# BottomSide.net
KiCad netlist of a schematic drawn in Altium Designer
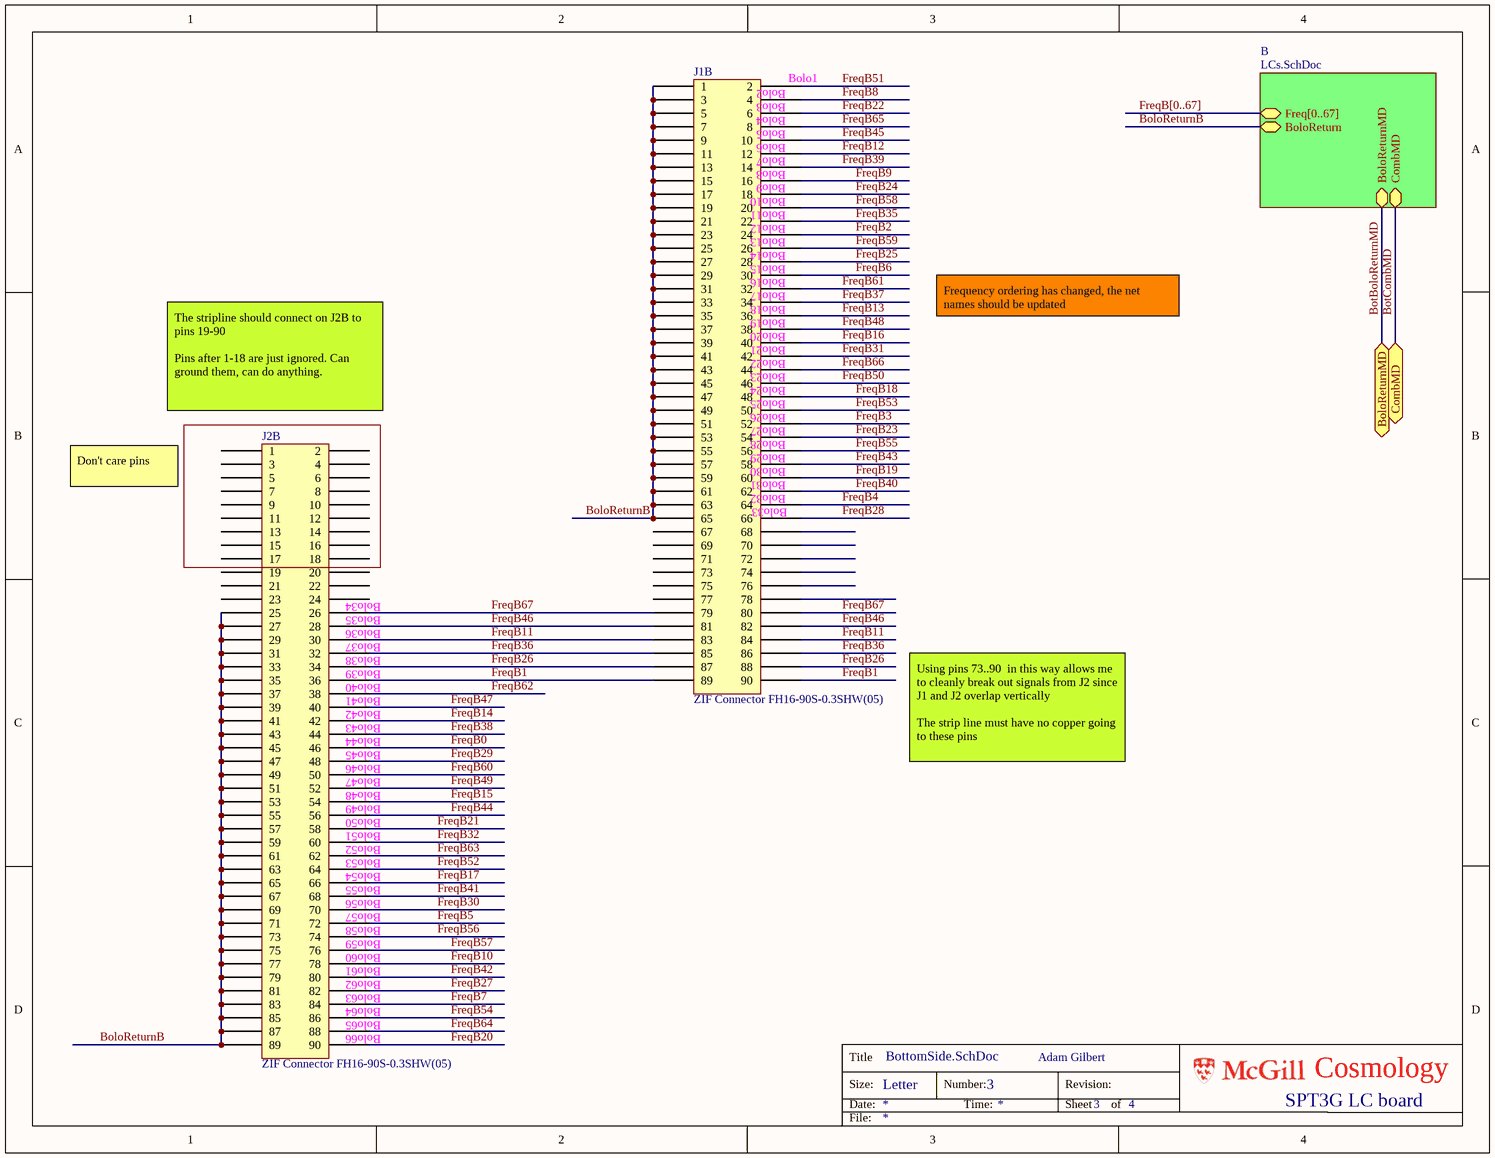
[diagram p0: BottomSide.SchDoc]

(export (version "E")
  (design (tool "Eeschema 10.0.6"))
  (components
    (comp (ref "J1B")
      (value "ZIF Connector FH16-90S-0.3SHW(05)")
      (footprint "LCBoard_ZIFCon")
      (libsource (lib "SPT3G_LCBoard") (part "LCboard_FH16-90S-0.3SHW(05)"))
    )
    (comp (ref "J2B")
      (value "ZIF Connector FH16-90S-0.3SHW(05)")
      (footprint "LCBoard_ZIFCon")
      (libsource (lib "SPT3G_LCBoard") (part "LCboard_FH16-90S-0.3SHW(05)"))
    )
  )
  (nets
    (net (code "3") (name "/BoloReturnB") (class "Default")
      (node (ref "J1B") (pin "1") (pinfunction "1_1") (pintype "passive"))
      (node (ref "J1B") (pin "11") (pinfunction "11_11") (pintype "passive"))
      (node (ref "J1B") (pin "13") (pinfunction "13_13") (pintype "passive"))
      (node (ref "J1B") (pin "15") (pinfunction "15_15") (pintype "passive"))
      (node (ref "J1B") (pin "17") (pinfunction "17_17") (pintype "passive"))
      (node (ref "J1B") (pin "19") (pinfunction "19_19") (pintype "passive"))
      (node (ref "J1B") (pin "21") (pinfunction "21_21") (pintype "passive"))
      (node (ref "J1B") (pin "23") (pinfunction "23_23") (pintype "passive"))
      (node (ref "J1B") (pin "25") (pinfunction "25_25") (pintype "passive"))
      (node (ref "J1B") (pin "27") (pinfunction "27_27") (pintype "passive"))
      (node (ref "J1B") (pin "29") (pinfunction "29_29") (pintype "passive"))
      (node (ref "J1B") (pin "3") (pinfunction "3_3") (pintype "passive"))
      (node (ref "J1B") (pin "31") (pinfunction "31_31") (pintype "passive"))
      (node (ref "J1B") (pin "33") (pinfunction "33_33") (pintype "passive"))
      (node (ref "J1B") (pin "35") (pinfunction "35_35") (pintype "passive"))
      (node (ref "J1B") (pin "37") (pinfunction "37_37") (pintype "passive"))
      (node (ref "J1B") (pin "39") (pinfunction "39_39") (pintype "passive"))
      (node (ref "J1B") (pin "41") (pinfunction "41_41") (pintype "passive"))
      (node (ref "J1B") (pin "43") (pinfunction "43_43") (pintype "passive"))
      (node (ref "J1B") (pin "45") (pinfunction "45_45") (pintype "passive"))
      (node (ref "J1B") (pin "47") (pinfunction "47_47") (pintype "passive"))
      (node (ref "J1B") (pin "49") (pinfunction "49_49") (pintype "passive"))
      (node (ref "J1B") (pin "5") (pinfunction "5_5") (pintype "passive"))
      (node (ref "J1B") (pin "51") (pinfunction "51_51") (pintype "passive"))
      (node (ref "J1B") (pin "53") (pinfunction "53_53") (pintype "passive"))
      (node (ref "J1B") (pin "55") (pinfunction "55_55") (pintype "passive"))
      (node (ref "J1B") (pin "57") (pinfunction "57_57") (pintype "passive"))
      (node (ref "J1B") (pin "59") (pinfunction "59_59") (pintype "passive"))
      (node (ref "J1B") (pin "61") (pinfunction "61_61") (pintype "passive"))
      (node (ref "J1B") (pin "63") (pinfunction "63_63") (pintype "passive"))
      (node (ref "J1B") (pin "65") (pinfunction "65_65") (pintype "passive"))
      (node (ref "J1B") (pin "7") (pinfunction "7_7") (pintype "passive"))
      (node (ref "J1B") (pin "9") (pinfunction "9_9") (pintype "passive"))
      (node (ref "J2B") (pin "25") (pinfunction "25_25") (pintype "passive"))
      (node (ref "J2B") (pin "27") (pinfunction "27_27") (pintype "passive"))
      (node (ref "J2B") (pin "29") (pinfunction "29_29") (pintype "passive"))
      (node (ref "J2B") (pin "31") (pinfunction "31_31") (pintype "passive"))
      (node (ref "J2B") (pin "33") (pinfunction "33_33") (pintype "passive"))
      (node (ref "J2B") (pin "35") (pinfunction "35_35") (pintype "passive"))
      (node (ref "J2B") (pin "37") (pinfunction "37_37") (pintype "passive"))
      (node (ref "J2B") (pin "39") (pinfunction "39_39") (pintype "passive"))
      (node (ref "J2B") (pin "41") (pinfunction "41_41") (pintype "passive"))
      (node (ref "J2B") (pin "43") (pinfunction "43_43") (pintype "passive"))
      (node (ref "J2B") (pin "45") (pinfunction "45_45") (pintype "passive"))
      (node (ref "J2B") (pin "47") (pinfunction "47_47") (pintype "passive"))
      (node (ref "J2B") (pin "49") (pinfunction "49_49") (pintype "passive"))
      (node (ref "J2B") (pin "51") (pinfunction "51_51") (pintype "passive"))
      (node (ref "J2B") (pin "53") (pinfunction "53_53") (pintype "passive"))
      (node (ref "J2B") (pin "55") (pinfunction "55_55") (pintype "passive"))
      (node (ref "J2B") (pin "57") (pinfunction "57_57") (pintype "passive"))
      (node (ref "J2B") (pin "59") (pinfunction "59_59") (pintype "passive"))
      (node (ref "J2B") (pin "61") (pinfunction "61_61") (pintype "passive"))
      (node (ref "J2B") (pin "63") (pinfunction "63_63") (pintype "passive"))
      (node (ref "J2B") (pin "65") (pinfunction "65_65") (pintype "passive"))
      (node (ref "J2B") (pin "67") (pinfunction "67_67") (pintype "passive"))
      (node (ref "J2B") (pin "69") (pinfunction "69_69") (pintype "passive"))
      (node (ref "J2B") (pin "71") (pinfunction "71_71") (pintype "passive"))
      (node (ref "J2B") (pin "73") (pinfunction "73_73") (pintype "passive"))
      (node (ref "J2B") (pin "75") (pinfunction "75_75") (pintype "passive"))
      (node (ref "J2B") (pin "77") (pinfunction "77_77") (pintype "passive"))
      (node (ref "J2B") (pin "79") (pinfunction "79_79") (pintype "passive"))
      (node (ref "J2B") (pin "81") (pinfunction "81_81") (pintype "passive"))
      (node (ref "J2B") (pin "83") (pinfunction "83_83") (pintype "passive"))
      (node (ref "J2B") (pin "85") (pinfunction "85_85") (pintype "passive"))
      (node (ref "J2B") (pin "87") (pinfunction "87_87") (pintype "passive"))
      (node (ref "J2B") (pin "89") (pinfunction "89_89") (pintype "passive"))
    )
    (net (code "6") (name "/FreqB0") (class "Default")
      (node (ref "J2B") (pin "46") (pinfunction "46_46") (pintype "passive"))
    )
    (net (code "7") (name "/FreqB1") (class "Default")
      (node (ref "J1B") (pin "89") (pinfunction "89_89") (pintype "passive"))
      (node (ref "J1B") (pin "90") (pinfunction "90_90") (pintype "passive"))
      (node (ref "J2B") (pin "36") (pinfunction "36_36") (pintype "passive"))
    )
    (net (code "8") (name "/FreqB2") (class "Default")
      (node (ref "J1B") (pin "24") (pinfunction "24_24") (pintype "passive"))
    )
    (net (code "9") (name "/FreqB3") (class "Default")
      (node (ref "J1B") (pin "52") (pinfunction "52_52") (pintype "passive"))
    )
    (net (code "10") (name "/FreqB4") (class "Default")
      (node (ref "J1B") (pin "64") (pinfunction "64_64") (pintype "passive"))
    )
    (net (code "11") (name "/FreqB5") (class "Default")
      (node (ref "J2B") (pin "72") (pinfunction "72_72") (pintype "passive"))
    )
    (net (code "12") (name "/FreqB6") (class "Default")
      (node (ref "J1B") (pin "30") (pinfunction "30_30") (pintype "passive"))
    )
    (net (code "13") (name "/FreqB7") (class "Default")
      (node (ref "J2B") (pin "84") (pinfunction "84_84") (pintype "passive"))
    )
    (net (code "14") (name "/FreqB8") (class "Default")
      (node (ref "J1B") (pin "4") (pinfunction "4_4") (pintype "passive"))
    )
    (net (code "15") (name "/FreqB9") (class "Default")
      (node (ref "J1B") (pin "16") (pinfunction "16_16") (pintype "passive"))
    )
    (net (code "16") (name "/FreqB10") (class "Default")
      (node (ref "J2B") (pin "78") (pinfunction "78_78") (pintype "passive"))
    )
    (net (code "17") (name "/FreqB11") (class "Default")
      (node (ref "J1B") (pin "83") (pinfunction "83_83") (pintype "passive"))
      (node (ref "J1B") (pin "84") (pinfunction "84_84") (pintype "passive"))
      (node (ref "J2B") (pin "30") (pinfunction "30_30") (pintype "passive"))
    )
    (net (code "18") (name "/FreqB12") (class "Default")
      (node (ref "J1B") (pin "12") (pinfunction "12_12") (pintype "passive"))
    )
    (net (code "19") (name "/FreqB13") (class "Default")
      (node (ref "J1B") (pin "36") (pinfunction "36_36") (pintype "passive"))
    )
    (net (code "20") (name "/FreqB14") (class "Default")
      (node (ref "J2B") (pin "42") (pinfunction "42_42") (pintype "passive"))
    )
    (net (code "21") (name "/FreqB15") (class "Default")
      (node (ref "J2B") (pin "54") (pinfunction "54_54") (pintype "passive"))
    )
    (net (code "22") (name "/FreqB16") (class "Default")
      (node (ref "J1B") (pin "40") (pinfunction "40_40") (pintype "passive"))
    )
    (net (code "23") (name "/FreqB17") (class "Default")
      (node (ref "J2B") (pin "66") (pinfunction "66_66") (pintype "passive"))
    )
    (net (code "24") (name "/FreqB18") (class "Default")
      (node (ref "J1B") (pin "48") (pinfunction "48_48") (pintype "passive"))
    )
    (net (code "25") (name "/FreqB19") (class "Default")
      (node (ref "J1B") (pin "60") (pinfunction "60_60") (pintype "passive"))
    )
    (net (code "26") (name "/FreqB20") (class "Default")
      (node (ref "J2B") (pin "90") (pinfunction "90_90") (pintype "passive"))
    )
    (net (code "27") (name "/FreqB21") (class "Default")
      (node (ref "J2B") (pin "58") (pinfunction "58_58") (pintype "passive"))
    )
    (net (code "28") (name "/FreqB22") (class "Default")
      (node (ref "J1B") (pin "6") (pinfunction "6_6") (pintype "passive"))
    )
    (net (code "29") (name "/FreqB23") (class "Default")
      (node (ref "J1B") (pin "54") (pinfunction "54_54") (pintype "passive"))
    )
    (net (code "30") (name "/FreqB24") (class "Default")
      (node (ref "J1B") (pin "18") (pinfunction "18_18") (pintype "passive"))
    )
    (net (code "31") (name "/FreqB25") (class "Default")
      (node (ref "J1B") (pin "28") (pinfunction "28_28") (pintype "passive"))
    )
    (net (code "32") (name "/FreqB26") (class "Default")
      (node (ref "J1B") (pin "87") (pinfunction "87_87") (pintype "passive"))
      (node (ref "J1B") (pin "88") (pinfunction "88_88") (pintype "passive"))
      (node (ref "J2B") (pin "34") (pinfunction "34_34") (pintype "passive"))
    )
    (net (code "33") (name "/FreqB27") (class "Default")
      (node (ref "J2B") (pin "82") (pinfunction "82_82") (pintype "passive"))
    )
    (net (code "34") (name "/FreqB28") (class "Default")
      (node (ref "J1B") (pin "66") (pinfunction "66_66") (pintype "passive"))
    )
    (net (code "35") (name "/FreqB29") (class "Default")
      (node (ref "J2B") (pin "48") (pinfunction "48_48") (pintype "passive"))
    )
    (net (code "36") (name "/FreqB30") (class "Default")
      (node (ref "J2B") (pin "70") (pinfunction "70_70") (pintype "passive"))
    )
    (net (code "37") (name "/FreqB31") (class "Default")
      (node (ref "J1B") (pin "42") (pinfunction "42_42") (pintype "passive"))
    )
    (net (code "38") (name "/FreqB32") (class "Default")
      (node (ref "J2B") (pin "60") (pinfunction "60_60") (pintype "passive"))
    )
    (net (code "39") (name "/FreqB35") (class "Default")
      (node (ref "J1B") (pin "22") (pinfunction "22_22") (pintype "passive"))
    )
    (net (code "40") (name "/FreqB36") (class "Default")
      (node (ref "J1B") (pin "85") (pinfunction "85_85") (pintype "passive"))
      (node (ref "J1B") (pin "86") (pinfunction "86_86") (pintype "passive"))
      (node (ref "J2B") (pin "32") (pinfunction "32_32") (pintype "passive"))
    )
    (net (code "41") (name "/FreqB37") (class "Default")
      (node (ref "J1B") (pin "34") (pinfunction "34_34") (pintype "passive"))
    )
    (net (code "42") (name "/FreqB38") (class "Default")
      (node (ref "J2B") (pin "44") (pinfunction "44_44") (pintype "passive"))
    )
    (net (code "43") (name "/FreqB39") (class "Default")
      (node (ref "J1B") (pin "14") (pinfunction "14_14") (pintype "passive"))
    )
    (net (code "44") (name "/FreqB40") (class "Default")
      (node (ref "J1B") (pin "62") (pinfunction "62_62") (pintype "passive"))
    )
    (net (code "45") (name "/FreqB41") (class "Default")
      (node (ref "J2B") (pin "68") (pinfunction "68_68") (pintype "passive"))
    )
    (net (code "46") (name "/FreqB42") (class "Default")
      (node (ref "J2B") (pin "80") (pinfunction "80_80") (pintype "passive"))
    )
    (net (code "47") (name "/FreqB43") (class "Default")
      (node (ref "J1B") (pin "58") (pinfunction "58_58") (pintype "passive"))
    )
    (net (code "48") (name "/FreqB44") (class "Default")
      (node (ref "J2B") (pin "56") (pinfunction "56_56") (pintype "passive"))
    )
    (net (code "49") (name "/FreqB45") (class "Default")
      (node (ref "J1B") (pin "10") (pinfunction "10_10") (pintype "passive"))
    )
    (net (code "50") (name "/FreqB46") (class "Default")
      (node (ref "J1B") (pin "81") (pinfunction "81_81") (pintype "passive"))
      (node (ref "J1B") (pin "82") (pinfunction "82_82") (pintype "passive"))
      (node (ref "J2B") (pin "28") (pinfunction "28_28") (pintype "passive"))
    )
    (net (code "51") (name "/FreqB47") (class "Default")
      (node (ref "J2B") (pin "40") (pinfunction "40_40") (pintype "passive"))
    )
    (net (code "52") (name "/FreqB48") (class "Default")
      (node (ref "J1B") (pin "38") (pinfunction "38_38") (pintype "passive"))
    )
    (net (code "53") (name "/FreqB49") (class "Default")
      (node (ref "J2B") (pin "52") (pinfunction "52_52") (pintype "passive"))
    )
    (net (code "54") (name "/FreqB50") (class "Default")
      (node (ref "J1B") (pin "46") (pinfunction "46_46") (pintype "passive"))
    )
    (net (code "55") (name "/FreqB51") (class "Default")
      (node (ref "J1B") (pin "2") (pinfunction "2_2") (pintype "passive"))
    )
    (net (code "56") (name "/FreqB52") (class "Default")
      (node (ref "J2B") (pin "64") (pinfunction "64_64") (pintype "passive"))
    )
    (net (code "57") (name "/FreqB53") (class "Default")
      (node (ref "J1B") (pin "50") (pinfunction "50_50") (pintype "passive"))
    )
    (net (code "58") (name "/FreqB54") (class "Default")
      (node (ref "J2B") (pin "86") (pinfunction "86_86") (pintype "passive"))
    )
    (net (code "59") (name "/FreqB55") (class "Default")
      (node (ref "J1B") (pin "56") (pinfunction "56_56") (pintype "passive"))
    )
    (net (code "60") (name "/FreqB56") (class "Default")
      (node (ref "J2B") (pin "74") (pinfunction "74_74") (pintype "passive"))
    )
    (net (code "61") (name "/FreqB57") (class "Default")
      (node (ref "J2B") (pin "76") (pinfunction "76_76") (pintype "passive"))
    )
    (net (code "62") (name "/FreqB58") (class "Default")
      (node (ref "J1B") (pin "20") (pinfunction "20_20") (pintype "passive"))
    )
    (net (code "63") (name "/FreqB59") (class "Default")
      (node (ref "J1B") (pin "26") (pinfunction "26_26") (pintype "passive"))
    )
    (net (code "64") (name "/FreqB60") (class "Default")
      (node (ref "J2B") (pin "50") (pinfunction "50_50") (pintype "passive"))
    )
    (net (code "65") (name "/FreqB61") (class "Default")
      (node (ref "J1B") (pin "32") (pinfunction "32_32") (pintype "passive"))
    )
    (net (code "66") (name "/FreqB62") (class "Default")
      (node (ref "J2B") (pin "38") (pinfunction "38_38") (pintype "passive"))
    )
    (net (code "67") (name "/FreqB63") (class "Default")
      (node (ref "J2B") (pin "62") (pinfunction "62_62") (pintype "passive"))
    )
    (net (code "68") (name "/FreqB64") (class "Default")
      (node (ref "J2B") (pin "88") (pinfunction "88_88") (pintype "passive"))
    )
    (net (code "69") (name "/FreqB65") (class "Default")
      (node (ref "J1B") (pin "8") (pinfunction "8_8") (pintype "passive"))
    )
    (net (code "70") (name "/FreqB66") (class "Default")
      (node (ref "J1B") (pin "44") (pinfunction "44_44") (pintype "passive"))
    )
    (net (code "71") (name "/FreqB67") (class "Default")
      (node (ref "J1B") (pin "79") (pinfunction "79_79") (pintype "passive"))
      (node (ref "J1B") (pin "80") (pinfunction "80_80") (pintype "passive"))
      (node (ref "J2B") (pin "26") (pinfunction "26_26") (pintype "passive"))
    )
    (net (code "73") (name "unconnected-(J1B-Pad67)") (class "Default")
      (node (ref "J1B") (pin "67") (pinfunction "67_67") (pintype "passive"))
    )
    (net (code "74") (name "unconnected-(J1B-Pad68)") (class "Default")
      (node (ref "J1B") (pin "68") (pinfunction "68_68") (pintype "passive"))
    )
    (net (code "75") (name "unconnected-(J1B-Pad69)") (class "Default")
      (node (ref "J1B") (pin "69") (pinfunction "69_69") (pintype "passive"))
    )
    (net (code "76") (name "unconnected-(J1B-Pad70)") (class "Default")
      (node (ref "J1B") (pin "70") (pinfunction "70_70") (pintype "passive"))
    )
    (net (code "77") (name "unconnected-(J1B-Pad71)") (class "Default")
      (node (ref "J1B") (pin "71") (pinfunction "71_71") (pintype "passive"))
    )
    (net (code "78") (name "unconnected-(J1B-Pad72)") (class "Default")
      (node (ref "J1B") (pin "72") (pinfunction "72_72") (pintype "passive"))
    )
    (net (code "79") (name "unconnected-(J1B-Pad73)") (class "Default")
      (node (ref "J1B") (pin "73") (pinfunction "73_73") (pintype "passive"))
    )
    (net (code "80") (name "unconnected-(J1B-Pad74)") (class "Default")
      (node (ref "J1B") (pin "74") (pinfunction "74_74") (pintype "passive"))
    )
    (net (code "81") (name "unconnected-(J1B-Pad75)") (class "Default")
      (node (ref "J1B") (pin "75") (pinfunction "75_75") (pintype "passive"))
    )
    (net (code "82") (name "unconnected-(J1B-Pad76)") (class "Default")
      (node (ref "J1B") (pin "76") (pinfunction "76_76") (pintype "passive"))
    )
    (net (code "83") (name "unconnected-(J1B-Pad77)") (class "Default")
      (node (ref "J1B") (pin "77") (pinfunction "77_77") (pintype "passive"))
    )
    (net (code "84") (name "unconnected-(J1B-Pad78)") (class "Default")
      (node (ref "J1B") (pin "78") (pinfunction "78_78") (pintype "passive"))
    )
    (net (code "85") (name "unconnected-(J2B-Pad1)") (class "Default")
      (node (ref "J2B") (pin "1") (pinfunction "1_1") (pintype "passive"))
    )
    (net (code "86") (name "unconnected-(J2B-Pad2)") (class "Default")
      (node (ref "J2B") (pin "2") (pinfunction "2_2") (pintype "passive"))
    )
    (net (code "87") (name "unconnected-(J2B-Pad3)") (class "Default")
      (node (ref "J2B") (pin "3") (pinfunction "3_3") (pintype "passive"))
    )
    (net (code "88") (name "unconnected-(J2B-Pad4)") (class "Default")
      (node (ref "J2B") (pin "4") (pinfunction "4_4") (pintype "passive"))
    )
    (net (code "89") (name "unconnected-(J2B-Pad5)") (class "Default")
      (node (ref "J2B") (pin "5") (pinfunction "5_5") (pintype "passive"))
    )
    (net (code "90") (name "unconnected-(J2B-Pad6)") (class "Default")
      (node (ref "J2B") (pin "6") (pinfunction "6_6") (pintype "passive"))
    )
    (net (code "91") (name "unconnected-(J2B-Pad7)") (class "Default")
      (node (ref "J2B") (pin "7") (pinfunction "7_7") (pintype "passive"))
    )
    (net (code "92") (name "unconnected-(J2B-Pad8)") (class "Default")
      (node (ref "J2B") (pin "8") (pinfunction "8_8") (pintype "passive"))
    )
    (net (code "93") (name "unconnected-(J2B-Pad9)") (class "Default")
      (node (ref "J2B") (pin "9") (pinfunction "9_9") (pintype "passive"))
    )
    (net (code "94") (name "unconnected-(J2B-Pad10)") (class "Default")
      (node (ref "J2B") (pin "10") (pinfunction "10_10") (pintype "passive"))
    )
    (net (code "95") (name "unconnected-(J2B-Pad11)") (class "Default")
      (node (ref "J2B") (pin "11") (pinfunction "11_11") (pintype "passive"))
    )
    (net (code "96") (name "unconnected-(J2B-Pad12)") (class "Default")
      (node (ref "J2B") (pin "12") (pinfunction "12_12") (pintype "passive"))
    )
    (net (code "97") (name "unconnected-(J2B-Pad13)") (class "Default")
      (node (ref "J2B") (pin "13") (pinfunction "13_13") (pintype "passive"))
    )
    (net (code "98") (name "unconnected-(J2B-Pad14)") (class "Default")
      (node (ref "J2B") (pin "14") (pinfunction "14_14") (pintype "passive"))
    )
    (net (code "99") (name "unconnected-(J2B-Pad15)") (class "Default")
      (node (ref "J2B") (pin "15") (pinfunction "15_15") (pintype "passive"))
    )
    (net (code "100") (name "unconnected-(J2B-Pad16)") (class "Default")
      (node (ref "J2B") (pin "16") (pinfunction "16_16") (pintype "passive"))
    )
    (net (code "101") (name "unconnected-(J2B-Pad17)") (class "Default")
      (node (ref "J2B") (pin "17") (pinfunction "17_17") (pintype "passive"))
    )
    (net (code "102") (name "unconnected-(J2B-Pad18)") (class "Default")
      (node (ref "J2B") (pin "18") (pinfunction "18_18") (pintype "passive"))
    )
    (net (code "103") (name "unconnected-(J2B-Pad19)") (class "Default")
      (node (ref "J2B") (pin "19") (pinfunction "19_19") (pintype "passive"))
    )
    (net (code "104") (name "unconnected-(J2B-Pad20)") (class "Default")
      (node (ref "J2B") (pin "20") (pinfunction "20_20") (pintype "passive"))
    )
    (net (code "105") (name "unconnected-(J2B-Pad21)") (class "Default")
      (node (ref "J2B") (pin "21") (pinfunction "21_21") (pintype "passive"))
    )
    (net (code "106") (name "unconnected-(J2B-Pad22)") (class "Default")
      (node (ref "J2B") (pin "22") (pinfunction "22_22") (pintype "passive"))
    )
    (net (code "107") (name "unconnected-(J2B-Pad23)") (class "Default")
      (node (ref "J2B") (pin "23") (pinfunction "23_23") (pintype "passive"))
    )
    (net (code "108") (name "unconnected-(J2B-Pad24)") (class "Default")
      (node (ref "J2B") (pin "24") (pinfunction "24_24") (pintype "passive"))
    )
  )
)
